# topboard.net
KiCad netlist of a schematic drawn in EAGLE
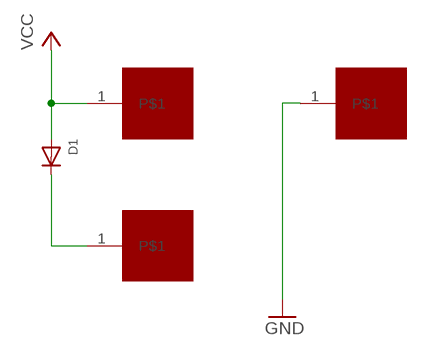
[diagram p0: schematic, sheet 1]

(export (version "E")
  (design (tool "Eeschema 10.0.6"))
  (components
    (comp (ref "D1")
      (value "DIODEDO-1N4148")
      (footprint "eagle-import:DO-1N4148")
      (libsource (lib "eagle-import") (part "DIODEDO-1N4148"))
    )
    (comp (ref "P1")
      (value "PAD")
      (footprint "eagle-import:PAD")
      (libsource (lib "eagle-import") (part "PAD"))
    )
    (comp (ref "P2")
      (value "PAD")
      (footprint "eagle-import:PAD")
      (libsource (lib "eagle-import") (part "PAD"))
    )
    (comp (ref "P3")
      (value "PAD")
      (footprint "eagle-import:PAD")
      (libsource (lib "eagle-import") (part "PAD"))
    )
  )
  (nets
    (net (code "1") (name "GND") (class "Default")
      (node (ref "P3") (pin "1") (pinfunction "P$1_1") (pintype "bidirectional"))
    )
    (net (code "2") (name "Net-(P1-P$1)") (class "Default")
      (node (ref "D1") (pin "C") (pinfunction "C_C") (pintype "passive"))
      (node (ref "P1") (pin "1") (pinfunction "P$1_1") (pintype "bidirectional"))
    )
    (net (code "3") (name "VCC") (class "Default")
      (node (ref "D1") (pin "A") (pinfunction "A_A") (pintype "passive"))
      (node (ref "P2") (pin "1") (pinfunction "P$1_1") (pintype "bidirectional"))
    )
  )
)
